# PK_MUV_sw.net
KiCad netlist of a schematic drawn in EAGLE
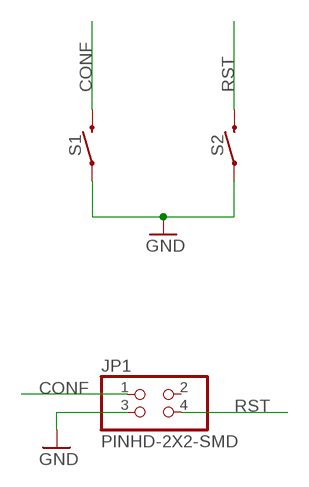
[diagram p0: schematic, sheet 1]

(export (version "E")
  (design (tool "Eeschema 10.0.6"))
  (components
    (comp (ref "JP1")
      (value "PINHD-2X2-SMD")
      (footprint "eagle-import:2X02SMD")
      (libsource (lib "eagle-import") (part "PINHD-2X2-SMD"))
    )
    (comp (ref "S1")
      (value "MOMENTARY-SWITCH-SPST-PTH-6.0MM-KIT")
      (footprint "eagle-import:TACTILE_SWITCH_PTH_6.0MM_KIT")
      (libsource (lib "eagle-import") (part "MOMENTARY-SWITCH-SPST-PTH-6.0MM-KIT"))
    )
    (comp (ref "S2")
      (value "MOMENTARY-SWITCH-SPST-PTH-6.0MM-KIT")
      (footprint "eagle-import:TACTILE_SWITCH_PTH_6.0MM_KIT")
      (libsource (lib "eagle-import") (part "MOMENTARY-SWITCH-SPST-PTH-6.0MM-KIT"))
    )
  )
  (nets
    (net (code "1") (name "/CONF") (class "Default")
      (node (ref "JP1") (pin "1") (pinfunction "1_1") (pintype "passive"))
      (node (ref "S1") (pin "3") (pinfunction "2_3") (pintype "passive"))
    )
    (net (code "2") (name "/RST") (class "Default")
      (node (ref "JP1") (pin "4") (pinfunction "4_4") (pintype "passive"))
      (node (ref "S2") (pin "3") (pinfunction "2_3") (pintype "passive"))
    )
    (net (code "3") (name "GND") (class "Default")
      (node (ref "JP1") (pin "3") (pinfunction "3_3") (pintype "passive"))
      (node (ref "S1") (pin "1") (pinfunction "1_1") (pintype "passive"))
      (node (ref "S2") (pin "1") (pinfunction "1_1") (pintype "passive"))
    )
    (net (code "4") (name "unconnected-(JP1-Pad2)") (class "Default")
      (node (ref "JP1") (pin "2") (pinfunction "2_2") (pintype "passive"))
    )
  )
)
